# core_XX8_THT.net
KiCad netlist of a schematic drawn in EAGLE
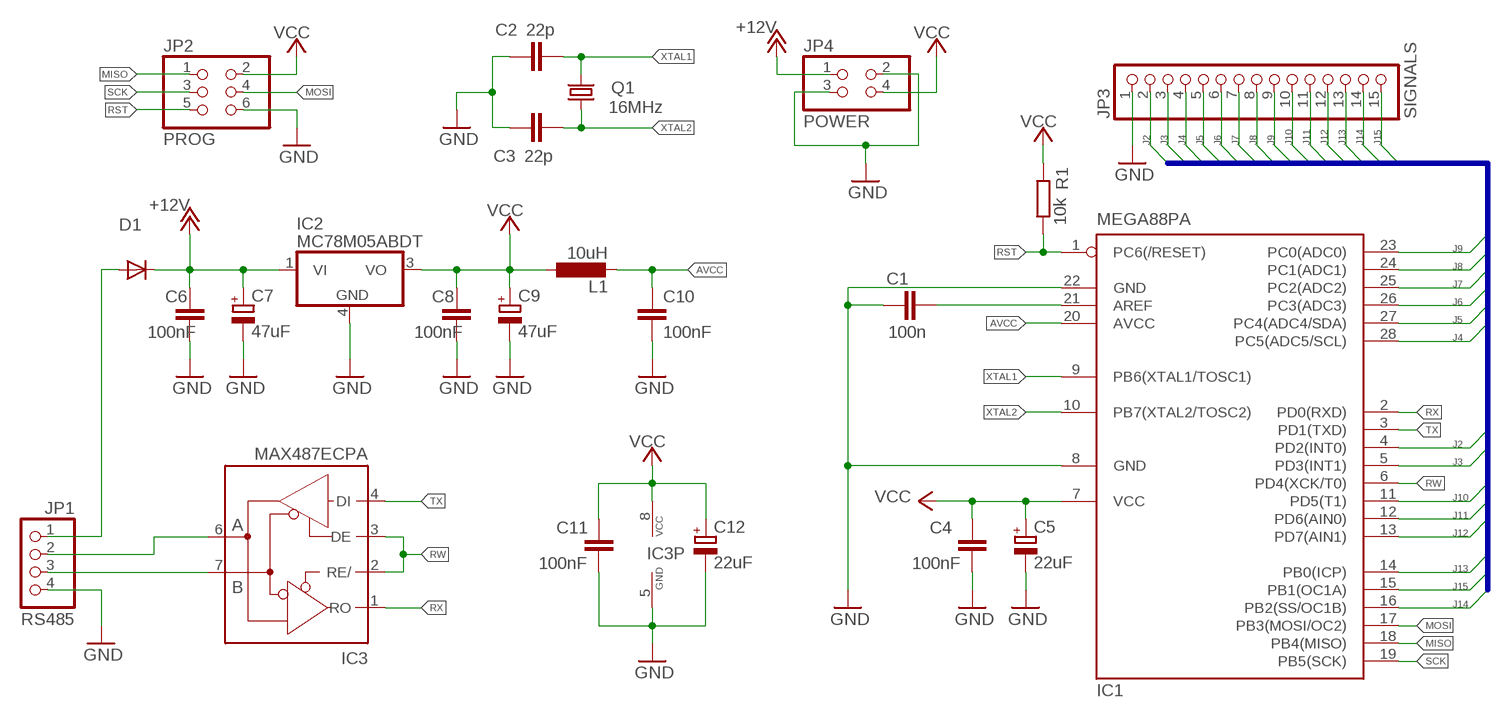
[diagram p0: schematic, sheet 1]

(export (version "E")
  (design (tool "Eeschema 10.0.6"))
  (components
    (comp (ref "C1")
      (value "100n")
      (footprint "eagle-import:C025-024X044")
      (libsource (lib "eagle-import") (part "C-EU025-024X044"))
    )
    (comp (ref "C2")
      (value "22p")
      (footprint "eagle-import:C025-024X044")
      (libsource (lib "eagle-import") (part "C-EU025-024X044"))
    )
    (comp (ref "C3")
      (value "22p")
      (footprint "eagle-import:C025-024X044")
      (libsource (lib "eagle-import") (part "C-EU025-024X044"))
    )
    (comp (ref "C4")
      (value "100nF")
      (footprint "eagle-import:C025-025X050")
      (libsource (lib "eagle-import") (part "C-EU025-025X050"))
    )
    (comp (ref "C5")
      (value "22uF")
      (footprint "eagle-import:E2-5")
      (libsource (lib "eagle-import") (part "CPOL-EUE2-5"))
    )
    (comp (ref "C6")
      (value "100nF")
      (footprint "eagle-import:C025-025X050")
      (libsource (lib "eagle-import") (part "C-EU025-025X050"))
    )
    (comp (ref "C7")
      (value "47uF")
      (footprint "eagle-import:E2,5-6")
      (libsource (lib "eagle-import") (part "CPOL-EUE2.5-6"))
    )
    (comp (ref "C8")
      (value "100nF")
      (footprint "eagle-import:C025-025X050")
      (libsource (lib "eagle-import") (part "C-EU025-025X050"))
    )
    (comp (ref "C9")
      (value "47uF")
      (footprint "eagle-import:E2,5-6")
      (libsource (lib "eagle-import") (part "CPOL-EUE2.5-6"))
    )
    (comp (ref "C10")
      (value "100nF")
      (footprint "eagle-import:C025-025X050")
      (libsource (lib "eagle-import") (part "C-EU025-025X050"))
    )
    (comp (ref "C11")
      (value "100nF")
      (footprint "eagle-import:C025-025X050")
      (libsource (lib "eagle-import") (part "C-EU025-025X050"))
    )
    (comp (ref "C12")
      (value "22uF")
      (footprint "eagle-import:E2-5")
      (libsource (lib "eagle-import") (part "CPOL-EUE2-5"))
    )
    (comp (ref "D1")
      (value "1N4002")
      (footprint "eagle-import:DO34-7")
      (libsource (lib "eagle-import") (part "BAS15"))
    )
    (comp (ref "IC1")
      (value "MEGA88PA")
      (footprint "eagle-import:DIL28-3")
      (libsource (lib "eagle-import") (part "MEGA8-P"))
    )
    (comp (ref "IC2")
      (value "MC78M05ABDT")
      (footprint "eagle-import:DPACK_3")
      (libsource (lib "eagle-import") (part "MC78M05ABDT"))
    )
    (comp (ref "IC3")
      (value "MAX487ECPA")
      (footprint "eagle-import:DIL08")
      (fields (field (name "MPN") "MAX481CPA+"))
      (libsource (lib "eagle-import") (part "MAX481CPA"))
    )
    (comp (ref "JP1")
      (value "RS485")
      (footprint "eagle-import:1X04")
      (libsource (lib "eagle-import") (part "PINHD-1X4"))
    )
    (comp (ref "JP2")
      (value "PROG")
      (footprint "eagle-import:2X03")
      (libsource (lib "eagle-import") (part "PINHD-2X3"))
    )
    (comp (ref "JP3")
      (value "SIGNALS")
      (footprint "eagle-import:1X15")
      (libsource (lib "eagle-import") (part "PINHD-1X15"))
    )
    (comp (ref "JP4")
      (value "POWER")
      (footprint "eagle-import:2X02")
      (libsource (lib "eagle-import") (part "PINHD-2X2"))
    )
    (comp (ref "L1")
      (value "10uH")
      (footprint "eagle-import:0207_12")
      (libsource (lib "eagle-import") (part "L-EU0207/12"))
    )
    (comp (ref "Q1")
      (value "16MHz")
      (footprint "eagle-import:HC49_S")
      (libsource (lib "eagle-import") (part "CRYSTALHC49S"))
    )
    (comp (ref "R1")
      (value "10k")
      (footprint "eagle-import:0204V")
      (libsource (lib "eagle-import") (part "R-EU_0204/2V"))
    )
  )
  (nets
    (net (code "1") (name "+12V") (class "Default")
      (node (ref "C6") (pin "1") (pinfunction "1_1") (pintype "passive"))
      (node (ref "C7") (pin "+") (pinfunction "+_+") (pintype "passive"))
      (node (ref "D1") (pin "C") (pinfunction "C_C") (pintype "passive"))
      (node (ref "IC2") (pin "1") (pinfunction "VI_1") (pintype "input"))
      (node (ref "JP4") (pin "1") (pinfunction "1_1") (pintype "passive"))
    )
    (net (code "2") (name "/J2") (class "Default")
      (node (ref "IC1") (pin "4") (pinfunction "PD2(INT0)_4") (pintype "bidirectional"))
      (node (ref "JP3") (pin "2") (pinfunction "2_2") (pintype "passive"))
    )
    (net (code "3") (name "/J3") (class "Default")
      (node (ref "IC1") (pin "5") (pinfunction "PD3(INT1)_5") (pintype "bidirectional"))
      (node (ref "JP3") (pin "3") (pinfunction "3_3") (pintype "passive"))
    )
    (net (code "4") (name "/J4") (class "Default")
      (node (ref "IC1") (pin "28") (pinfunction "PC5(ADC5/SCL)_28") (pintype "bidirectional"))
      (node (ref "JP3") (pin "4") (pinfunction "4_4") (pintype "passive"))
    )
    (net (code "5") (name "/J5") (class "Default")
      (node (ref "IC1") (pin "27") (pinfunction "PC4(ADC4/SDA)_27") (pintype "bidirectional"))
      (node (ref "JP3") (pin "5") (pinfunction "5_5") (pintype "passive"))
    )
    (net (code "6") (name "/J6") (class "Default")
      (node (ref "IC1") (pin "26") (pinfunction "PC3(ADC3)_26") (pintype "bidirectional"))
      (node (ref "JP3") (pin "6") (pinfunction "6_6") (pintype "passive"))
    )
    (net (code "7") (name "/J7") (class "Default")
      (node (ref "IC1") (pin "25") (pinfunction "PC2(ADC2)_25") (pintype "bidirectional"))
      (node (ref "JP3") (pin "7") (pinfunction "7_7") (pintype "passive"))
    )
    (net (code "8") (name "/J8") (class "Default")
      (node (ref "IC1") (pin "24") (pinfunction "PC1(ADC1)_24") (pintype "bidirectional"))
      (node (ref "JP3") (pin "8") (pinfunction "8_8") (pintype "passive"))
    )
    (net (code "9") (name "/J9") (class "Default")
      (node (ref "IC1") (pin "23") (pinfunction "PC0(ADC0)_23") (pintype "bidirectional"))
      (node (ref "JP3") (pin "9") (pinfunction "9_9") (pintype "passive"))
    )
    (net (code "10") (name "/J10") (class "Default")
      (node (ref "IC1") (pin "11") (pinfunction "PD5(T1)_11") (pintype "bidirectional"))
      (node (ref "JP3") (pin "10") (pinfunction "10_10") (pintype "passive"))
    )
    (net (code "11") (name "/J11") (class "Default")
      (node (ref "IC1") (pin "12") (pinfunction "PD6(AIN0)_12") (pintype "bidirectional"))
      (node (ref "JP3") (pin "11") (pinfunction "11_11") (pintype "passive"))
    )
    (net (code "12") (name "/J12") (class "Default")
      (node (ref "IC1") (pin "13") (pinfunction "PD7(AIN1)_13") (pintype "bidirectional"))
      (node (ref "JP3") (pin "12") (pinfunction "12_12") (pintype "passive"))
    )
    (net (code "13") (name "/J13") (class "Default")
      (node (ref "IC1") (pin "14") (pinfunction "PB0(ICP)_14") (pintype "bidirectional"))
      (node (ref "JP3") (pin "13") (pinfunction "13_13") (pintype "passive"))
    )
    (net (code "14") (name "/J14") (class "Default")
      (node (ref "IC1") (pin "16") (pinfunction "PB2(SS/OC1B)_16") (pintype "bidirectional"))
      (node (ref "JP3") (pin "14") (pinfunction "14_14") (pintype "passive"))
    )
    (net (code "15") (name "/J15") (class "Default")
      (node (ref "IC1") (pin "15") (pinfunction "PB1(OC1A)_15") (pintype "bidirectional"))
      (node (ref "JP3") (pin "15") (pinfunction "15_15") (pintype "passive"))
    )
    (net (code "16") (name "AVCC") (class "Default")
      (node (ref "C10") (pin "1") (pinfunction "1_1") (pintype "passive"))
      (node (ref "IC1") (pin "20") (pinfunction "AVCC_20") (pintype "power_in"))
      (node (ref "L1") (pin "2") (pinfunction "2_2") (pintype "passive"))
    )
    (net (code "17") (name "GND") (class "Default")
      (node (ref "C1") (pin "1") (pinfunction "1_1") (pintype "passive"))
      (node (ref "C10") (pin "2") (pinfunction "2_2") (pintype "passive"))
      (node (ref "C11") (pin "2") (pinfunction "2_2") (pintype "passive"))
      (node (ref "C12") (pin "-") (pinfunction "-_-") (pintype "passive"))
      (node (ref "C2") (pin "1") (pinfunction "1_1") (pintype "passive"))
      (node (ref "C3") (pin "1") (pinfunction "1_1") (pintype "passive"))
      (node (ref "C4") (pin "2") (pinfunction "2_2") (pintype "passive"))
      (node (ref "C5") (pin "-") (pinfunction "-_-") (pintype "passive"))
      (node (ref "C6") (pin "2") (pinfunction "2_2") (pintype "passive"))
      (node (ref "C7") (pin "-") (pinfunction "-_-") (pintype "passive"))
      (node (ref "C8") (pin "2") (pinfunction "2_2") (pintype "passive"))
      (node (ref "C9") (pin "-") (pinfunction "-_-") (pintype "passive"))
      (node (ref "IC1") (pin "22") (pinfunction "GND_22") (pintype "power_in"))
      (node (ref "IC1") (pin "8") (pinfunction "GND_8") (pintype "power_in"))
      (node (ref "IC2") (pin "4") (pinfunction "GND_4") (pintype "passive"))
      (node (ref "IC3") (pin "5") (pinfunction "GND_5") (pintype "power_in"))
      (node (ref "JP1") (pin "4") (pinfunction "4_4") (pintype "passive"))
      (node (ref "JP2") (pin "6") (pinfunction "6_6") (pintype "passive"))
      (node (ref "JP3") (pin "1") (pinfunction "1_1") (pintype "passive"))
      (node (ref "JP4") (pin "2") (pinfunction "2_2") (pintype "passive"))
      (node (ref "JP4") (pin "3") (pinfunction "3_3") (pintype "passive"))
    )
    (net (code "18") (name "MISO") (class "Default")
      (node (ref "IC1") (pin "18") (pinfunction "PB4(MISO)_18") (pintype "bidirectional"))
      (node (ref "JP2") (pin "1") (pinfunction "1_1") (pintype "passive"))
    )
    (net (code "19") (name "MOSI") (class "Default")
      (node (ref "IC1") (pin "17") (pinfunction "PB3(MOSI/OC2)_17") (pintype "bidirectional"))
      (node (ref "JP2") (pin "4") (pinfunction "4_4") (pintype "passive"))
    )
    (net (code "20") (name "Net-(D1-PadA)") (class "Default")
      (node (ref "D1") (pin "A") (pinfunction "A_A") (pintype "passive"))
      (node (ref "JP1") (pin "1") (pinfunction "1_1") (pintype "passive"))
    )
    (net (code "21") (name "Net-(IC1-AREF)") (class "Default")
      (node (ref "C1") (pin "2") (pinfunction "2_2") (pintype "passive"))
      (node (ref "IC1") (pin "21") (pinfunction "AREF_21") (pintype "passive"))
    )
    (net (code "22") (name "Net-(IC3A-A)") (class "Default")
      (node (ref "IC3") (pin "6") (pinfunction "A_6") (pintype "passive"))
      (node (ref "JP1") (pin "2") (pinfunction "2_2") (pintype "passive"))
    )
    (net (code "23") (name "Net-(IC3A-B)") (class "Default")
      (node (ref "IC3") (pin "7") (pinfunction "B_7") (pintype "passive"))
      (node (ref "JP1") (pin "3") (pinfunction "3_3") (pintype "passive"))
    )
    (net (code "24") (name "RST") (class "Default")
      (node (ref "IC1") (pin "1") (pinfunction "PC6(/RESET)_1") (pintype "bidirectional"))
      (node (ref "JP2") (pin "5") (pinfunction "5_5") (pintype "passive"))
      (node (ref "R1") (pin "1") (pinfunction "1_1") (pintype "passive"))
    )
    (net (code "25") (name "RW") (class "Default")
      (node (ref "IC1") (pin "6") (pinfunction "PD4(XCK/T0)_6") (pintype "bidirectional"))
      (node (ref "IC3") (pin "2") (pinfunction "RE/_2") (pintype "input"))
      (node (ref "IC3") (pin "3") (pinfunction "DE_3") (pintype "input"))
    )
    (net (code "26") (name "RX") (class "Default")
      (node (ref "IC1") (pin "2") (pinfunction "PD0(RXD)_2") (pintype "bidirectional"))
      (node (ref "IC3") (pin "1") (pinfunction "RO_1") (pintype "output"))
    )
    (net (code "27") (name "SCK") (class "Default")
      (node (ref "IC1") (pin "19") (pinfunction "PB5(SCK)_19") (pintype "bidirectional"))
      (node (ref "JP2") (pin "3") (pinfunction "3_3") (pintype "passive"))
    )
    (net (code "28") (name "TX") (class "Default")
      (node (ref "IC1") (pin "3") (pinfunction "PD1(TXD)_3") (pintype "bidirectional"))
      (node (ref "IC3") (pin "4") (pinfunction "DI_4") (pintype "input"))
    )
    (net (code "29") (name "VCC") (class "Default")
      (node (ref "C11") (pin "1") (pinfunction "1_1") (pintype "passive"))
      (node (ref "C12") (pin "+") (pinfunction "+_+") (pintype "passive"))
      (node (ref "C4") (pin "1") (pinfunction "1_1") (pintype "passive"))
      (node (ref "C5") (pin "+") (pinfunction "+_+") (pintype "passive"))
      (node (ref "C8") (pin "1") (pinfunction "1_1") (pintype "passive"))
      (node (ref "C9") (pin "+") (pinfunction "+_+") (pintype "passive"))
      (node (ref "IC1") (pin "7") (pinfunction "VCC_7") (pintype "power_in"))
      (node (ref "IC2") (pin "3") (pinfunction "VO_3") (pintype "passive"))
      (node (ref "IC3") (pin "8") (pinfunction "VCC_8") (pintype "power_in"))
      (node (ref "JP2") (pin "2") (pinfunction "2_2") (pintype "passive"))
      (node (ref "JP4") (pin "4") (pinfunction "4_4") (pintype "passive"))
      (node (ref "L1") (pin "1") (pinfunction "1_1") (pintype "passive"))
      (node (ref "R1") (pin "2") (pinfunction "2_2") (pintype "passive"))
    )
    (net (code "30") (name "XTAL1") (class "Default")
      (node (ref "C2") (pin "2") (pinfunction "2_2") (pintype "passive"))
      (node (ref "IC1") (pin "9") (pinfunction "PB6(XTAL1/TOSC1)_9") (pintype "bidirectional"))
      (node (ref "Q1") (pin "2") (pinfunction "2_2") (pintype "passive"))
    )
    (net (code "31") (name "XTAL2") (class "Default")
      (node (ref "C3") (pin "2") (pinfunction "2_2") (pintype "passive"))
      (node (ref "IC1") (pin "10") (pinfunction "PB7(XTAL2/TOSC2)_10") (pintype "bidirectional"))
      (node (ref "Q1") (pin "1") (pinfunction "1_1") (pintype "passive"))
    )
  )
)
